# senseBox-OLED_v21.net
KiCad netlist of a schematic drawn in EAGLE
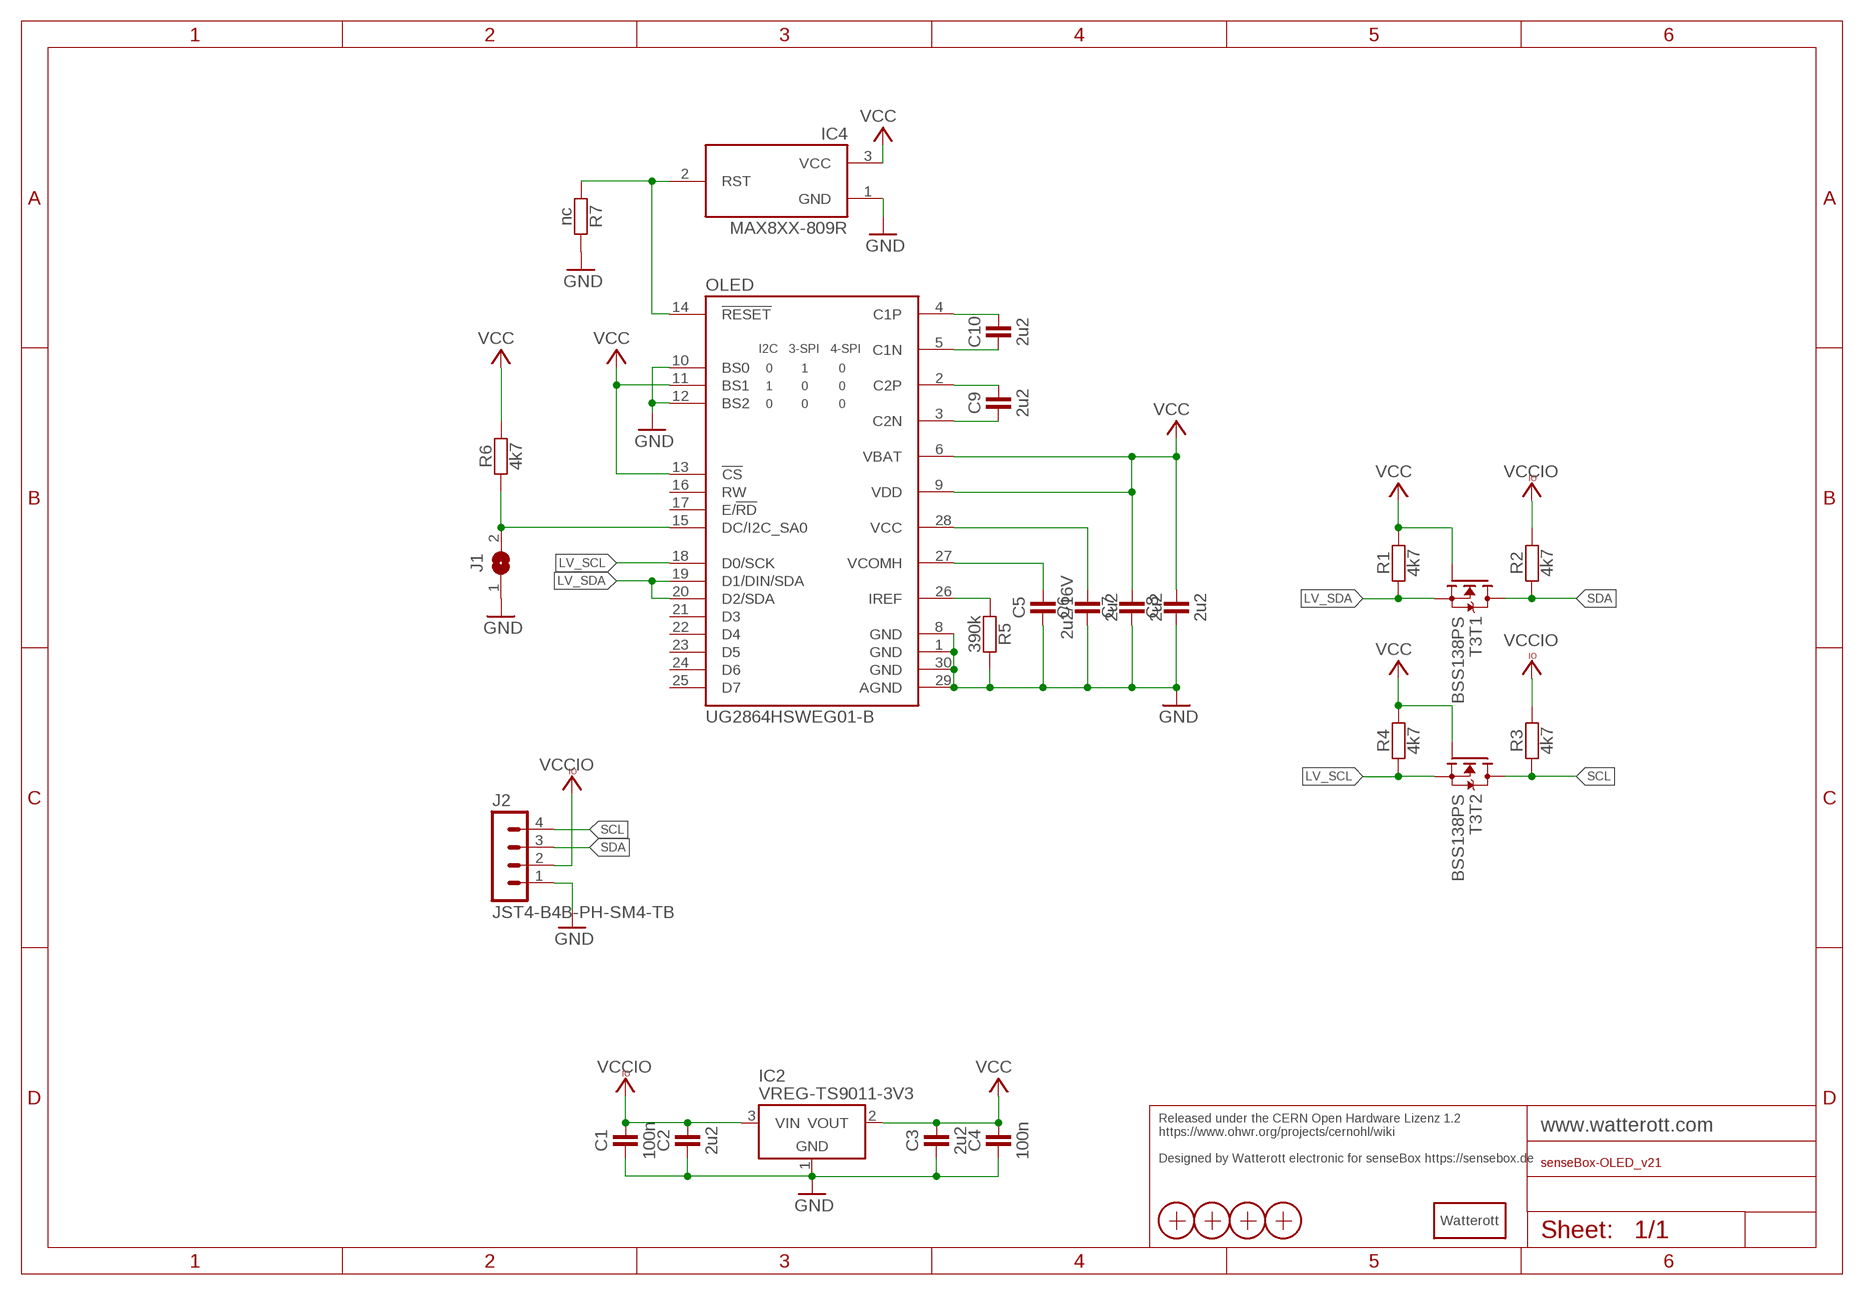
[diagram p0: schematic, sheet 1]

(export (version "E")
  (design (tool "Eeschema 10.0.6"))
  (components
    (comp (ref "C1")
      (value "100n")
      (footprint "eagle-import:C0402")
      (libsource (lib "eagle-import") (part "CAPACITOR-0402"))
    )
    (comp (ref "C2")
      (value "2u2")
      (footprint "eagle-import:C0402")
      (libsource (lib "eagle-import") (part "CAPACITOR-0402"))
    )
    (comp (ref "C3")
      (value "2u2")
      (footprint "eagle-import:C0402")
      (libsource (lib "eagle-import") (part "CAPACITOR-0402"))
    )
    (comp (ref "C4")
      (value "100n")
      (footprint "eagle-import:C0402")
      (libsource (lib "eagle-import") (part "CAPACITOR-0402"))
    )
    (comp (ref "C5")
      (value "2u2/16V")
      (footprint "eagle-import:C0402")
      (libsource (lib "eagle-import") (part "CAPACITOR-0402"))
    )
    (comp (ref "C6")
      (value "2u2")
      (footprint "eagle-import:C0402")
      (libsource (lib "eagle-import") (part "CAPACITOR-0402"))
    )
    (comp (ref "C7")
      (value "2u2")
      (footprint "eagle-import:C0402")
      (libsource (lib "eagle-import") (part "CAPACITOR-0402"))
    )
    (comp (ref "C8")
      (value "2u2")
      (footprint "eagle-import:C0402")
      (libsource (lib "eagle-import") (part "CAPACITOR-0402"))
    )
    (comp (ref "C9")
      (value "2u2")
      (footprint "eagle-import:C0402")
      (libsource (lib "eagle-import") (part "CAPACITOR-0402"))
    )
    (comp (ref "C10")
      (value "2u2")
      (footprint "eagle-import:C0402")
      (libsource (lib "eagle-import") (part "CAPACITOR-0402"))
    )
    (comp (ref "IC2")
      (value "VREG-TS9011-3V3")
      (footprint "eagle-import:SOT23")
      (libsource (lib "eagle-import") (part "VREG-TS9011-3V3"))
    )
    (comp (ref "IC4")
      (value "MAX8XX-809R")
      (footprint "eagle-import:SOT23")
      (libsource (lib "eagle-import") (part "MAX8XX-809R"))
    )
    (comp (ref "J1")
      (value "JUMPER2-0402-NC")
      (footprint "eagle-import:JUMPER2-0402_NC")
      (libsource (lib "eagle-import") (part "JUMPER2-0402-NC"))
    )
    (comp (ref "J2")
      (value "JST4-B4B-PH-SM4-TB")
      (footprint "eagle-import:JST_B4B-PH-SM4-TB")
      (libsource (lib "eagle-import") (part "JST4-B4B-PH-SM4-TB"))
    )
    (comp (ref "LOGO1")
      (value "LOGO_SPARK-2")
      (footprint "eagle-import:SPARK_2MM")
      (libsource (lib "eagle-import") (part "LOGO_SPARK-2"))
    )
    (comp (ref "OLED")
      (value "UG2864HSWEG01-B")
      (footprint "eagle-import:UG2864HSWEG01_BOT")
      (libsource (lib "eagle-import") (part "UG2864HSWEG01-B"))
    )
    (comp (ref "R1")
      (value "4k7")
      (footprint "eagle-import:C0402")
      (libsource (lib "eagle-import") (part "RESISTOR-0402"))
    )
    (comp (ref "R2")
      (value "4k7")
      (footprint "eagle-import:C0402")
      (libsource (lib "eagle-import") (part "RESISTOR-0402"))
    )
    (comp (ref "R3")
      (value "4k7")
      (footprint "eagle-import:C0402")
      (libsource (lib "eagle-import") (part "RESISTOR-0402"))
    )
    (comp (ref "R4")
      (value "4k7")
      (footprint "eagle-import:C0402")
      (libsource (lib "eagle-import") (part "RESISTOR-0402"))
    )
    (comp (ref "R5")
      (value "390k")
      (footprint "eagle-import:C0402")
      (libsource (lib "eagle-import") (part "RESISTOR-0402"))
    )
    (comp (ref "R6")
      (value "4k7")
      (footprint "eagle-import:C0402")
      (libsource (lib "eagle-import") (part "RESISTOR-0402"))
    )
    (comp (ref "R7")
      (value "nc")
      (footprint "eagle-import:C0402")
      (libsource (lib "eagle-import") (part "RESISTOR-0402"))
    )
    (comp (ref "T3")
      (value "BSS138PS")
      (footprint "eagle-import:SOT363")
      (libsource (lib "eagle-import") (part "BSS138PS"))
    )
    (comp (ref "X1")
      (value "PASSER-07")
      (footprint "eagle-import:PASSER_07MM")
      (libsource (lib "eagle-import") (part "PASSER-07"))
    )
    (comp (ref "X2")
      (value "PASSER-07")
      (footprint "eagle-import:PASSER_07MM")
      (libsource (lib "eagle-import") (part "PASSER-07"))
    )
    (comp (ref "X3")
      (value "PASSER-07")
      (footprint "eagle-import:PASSER_07MM")
      (libsource (lib "eagle-import") (part "PASSER-07"))
    )
    (comp (ref "X4")
      (value "PASSER-07")
      (footprint "eagle-import:PASSER_07MM")
      (libsource (lib "eagle-import") (part "PASSER-07"))
    )
  )
  (nets
    (net (code "1") (name "GND") (class "Default")
      (node (ref "C1") (pin "1") (pinfunction "1_1") (pintype "passive"))
      (node (ref "C2") (pin "1") (pinfunction "1_1") (pintype "passive"))
      (node (ref "C3") (pin "1") (pinfunction "1_1") (pintype "passive"))
      (node (ref "C4") (pin "1") (pinfunction "1_1") (pintype "passive"))
      (node (ref "C5") (pin "1") (pinfunction "1_1") (pintype "passive"))
      (node (ref "C6") (pin "1") (pinfunction "1_1") (pintype "passive"))
      (node (ref "C7") (pin "1") (pinfunction "1_1") (pintype "passive"))
      (node (ref "C8") (pin "1") (pinfunction "1_1") (pintype "passive"))
      (node (ref "IC2") (pin "1") (pinfunction "GND_1") (pintype "power_in"))
      (node (ref "IC4") (pin "1") (pinfunction "GND_1") (pintype "power_in"))
      (node (ref "J1") (pin "1") (pinfunction "1_1") (pintype "passive"))
      (node (ref "J2") (pin "1") (pinfunction "1_1") (pintype "passive"))
      (node (ref "OLED") (pin "1") (pinfunction "GND_1") (pintype "power_in"))
      (node (ref "OLED") (pin "10") (pinfunction "BS0_10") (pintype "input"))
      (node (ref "OLED") (pin "12") (pinfunction "BS2_12") (pintype "input"))
      (node (ref "OLED") (pin "29") (pinfunction "AGND_29") (pintype "power_in"))
      (node (ref "OLED") (pin "30") (pinfunction "GND_30") (pintype "power_in"))
      (node (ref "OLED") (pin "8") (pinfunction "GND_8") (pintype "power_in"))
      (node (ref "R5") (pin "2") (pinfunction "2_2") (pintype "passive"))
      (node (ref "R7") (pin "2") (pinfunction "2_2") (pintype "passive"))
    )
    (net (code "2") (name "LV_SCL") (class "Default")
      (node (ref "OLED") (pin "18") (pinfunction "D0/SCK_18") (pintype "bidirectional"))
      (node (ref "R4") (pin "1") (pinfunction "1_1") (pintype "passive"))
      (node (ref "T3") (pin "4") (pinfunction "S_4") (pintype "passive"))
    )
    (net (code "3") (name "LV_SDA") (class "Default")
      (node (ref "OLED") (pin "19") (pinfunction "D1/DIN/SDA_19") (pintype "bidirectional"))
      (node (ref "OLED") (pin "20") (pinfunction "D2/SDA_20") (pintype "bidirectional"))
      (node (ref "R1") (pin "1") (pinfunction "1_1") (pintype "passive"))
      (node (ref "T3") (pin "1") (pinfunction "S_1") (pintype "passive"))
    )
    (net (code "4") (name "Net-(IC4-RST)") (class "Default")
      (node (ref "IC4") (pin "2") (pinfunction "RST_2") (pintype "output"))
      (node (ref "OLED") (pin "14") (pinfunction "~{RESET}_14") (pintype "input"))
      (node (ref "R7") (pin "1") (pinfunction "1_1") (pintype "passive"))
    )
    (net (code "5") (name "Net-(OLED-C1N)") (class "Default")
      (node (ref "C10") (pin "1") (pinfunction "1_1") (pintype "passive"))
      (node (ref "OLED") (pin "5") (pinfunction "C1N_5") (pintype "passive"))
    )
    (net (code "6") (name "Net-(OLED-C1P)") (class "Default")
      (node (ref "C10") (pin "2") (pinfunction "2_2") (pintype "passive"))
      (node (ref "OLED") (pin "4") (pinfunction "C1P_4") (pintype "passive"))
    )
    (net (code "7") (name "Net-(OLED-C2N)") (class "Default")
      (node (ref "C9") (pin "1") (pinfunction "1_1") (pintype "passive"))
      (node (ref "OLED") (pin "3") (pinfunction "C2N_3") (pintype "passive"))
    )
    (net (code "8") (name "Net-(OLED-C2P)") (class "Default")
      (node (ref "C9") (pin "2") (pinfunction "2_2") (pintype "passive"))
      (node (ref "OLED") (pin "2") (pinfunction "C2P_2") (pintype "passive"))
    )
    (net (code "9") (name "Net-(OLED-DC{slash}I2C_SA0)") (class "Default")
      (node (ref "J1") (pin "2") (pinfunction "2_2") (pintype "passive"))
      (node (ref "OLED") (pin "15") (pinfunction "DC/I2C_SA0_15") (pintype "input"))
      (node (ref "R6") (pin "1") (pinfunction "1_1") (pintype "passive"))
    )
    (net (code "10") (name "Net-(OLED-IREF)") (class "Default")
      (node (ref "OLED") (pin "26") (pinfunction "IREF_26") (pintype "passive"))
      (node (ref "R5") (pin "1") (pinfunction "1_1") (pintype "passive"))
    )
    (net (code "11") (name "Net-(OLED-VCC)") (class "Default")
      (node (ref "C6") (pin "2") (pinfunction "2_2") (pintype "passive"))
      (node (ref "OLED") (pin "28") (pinfunction "VCC_28") (pintype "power_in"))
    )
    (net (code "12") (name "Net-(OLED-VCOMH)") (class "Default")
      (node (ref "C5") (pin "2") (pinfunction "2_2") (pintype "passive"))
      (node (ref "OLED") (pin "27") (pinfunction "VCOMH_27") (pintype "power_in"))
    )
    (net (code "13") (name "SCL") (class "Default")
      (node (ref "J2") (pin "4") (pinfunction "4_4") (pintype "passive"))
      (node (ref "R3") (pin "1") (pinfunction "1_1") (pintype "passive"))
      (node (ref "T3") (pin "3") (pinfunction "D_3") (pintype "passive"))
    )
    (net (code "14") (name "SDA") (class "Default")
      (node (ref "J2") (pin "3") (pinfunction "3_3") (pintype "passive"))
      (node (ref "R2") (pin "1") (pinfunction "1_1") (pintype "passive"))
      (node (ref "T3") (pin "6") (pinfunction "D_6") (pintype "passive"))
    )
    (net (code "15") (name "VCC") (class "Default")
      (node (ref "C3") (pin "2") (pinfunction "2_2") (pintype "passive"))
      (node (ref "C4") (pin "2") (pinfunction "2_2") (pintype "passive"))
      (node (ref "C7") (pin "2") (pinfunction "2_2") (pintype "passive"))
      (node (ref "C8") (pin "2") (pinfunction "2_2") (pintype "passive"))
      (node (ref "IC2") (pin "2") (pinfunction "VOUT_2") (pintype "power_in"))
      (node (ref "IC4") (pin "3") (pinfunction "VCC_3") (pintype "power_in"))
      (node (ref "OLED") (pin "11") (pinfunction "BS1_11") (pintype "input"))
      (node (ref "OLED") (pin "13") (pinfunction "~{CS}_13") (pintype "input"))
      (node (ref "OLED") (pin "6") (pinfunction "VBAT_6") (pintype "power_in"))
      (node (ref "OLED") (pin "9") (pinfunction "VDD_9") (pintype "power_in"))
      (node (ref "R1") (pin "2") (pinfunction "2_2") (pintype "passive"))
      (node (ref "R4") (pin "2") (pinfunction "2_2") (pintype "passive"))
      (node (ref "R6") (pin "2") (pinfunction "2_2") (pintype "passive"))
      (node (ref "T3") (pin "2") (pinfunction "G_2") (pintype "passive"))
      (node (ref "T3") (pin "5") (pinfunction "G_5") (pintype "passive"))
    )
    (net (code "16") (name "VCCIO") (class "Default")
      (node (ref "C1") (pin "2") (pinfunction "2_2") (pintype "passive"))
      (node (ref "C2") (pin "2") (pinfunction "2_2") (pintype "passive"))
      (node (ref "IC2") (pin "3") (pinfunction "VIN_3") (pintype "power_in"))
      (node (ref "J2") (pin "2") (pinfunction "2_2") (pintype "passive"))
      (node (ref "R2") (pin "2") (pinfunction "2_2") (pintype "passive"))
      (node (ref "R3") (pin "2") (pinfunction "2_2") (pintype "passive"))
    )
    (net (code "17") (name "unconnected-(OLED-D3-Pad21)") (class "Default")
      (node (ref "OLED") (pin "21") (pinfunction "D3_21") (pintype "bidirectional"))
    )
    (net (code "18") (name "unconnected-(OLED-D4-Pad22)") (class "Default")
      (node (ref "OLED") (pin "22") (pinfunction "D4_22") (pintype "bidirectional"))
    )
    (net (code "19") (name "unconnected-(OLED-D5-Pad23)") (class "Default")
      (node (ref "OLED") (pin "23") (pinfunction "D5_23") (pintype "bidirectional"))
    )
    (net (code "20") (name "unconnected-(OLED-D6-Pad24)") (class "Default")
      (node (ref "OLED") (pin "24") (pinfunction "D6_24") (pintype "bidirectional"))
    )
    (net (code "21") (name "unconnected-(OLED-D7-Pad25)") (class "Default")
      (node (ref "OLED") (pin "25") (pinfunction "D7_25") (pintype "bidirectional"))
    )
    (net (code "22") (name "unconnected-(OLED-E{slash}~{RD}-Pad17)") (class "Default")
      (node (ref "OLED") (pin "17") (pinfunction "E/~{RD}_17") (pintype "bidirectional"))
    )
    (net (code "23") (name "unconnected-(OLED-RW-Pad16)") (class "Default")
      (node (ref "OLED") (pin "16") (pinfunction "RW_16") (pintype "bidirectional"))
    )
  )
)
